# feelerBox1_2.net
KiCad netlist of a schematic drawn in EAGLE
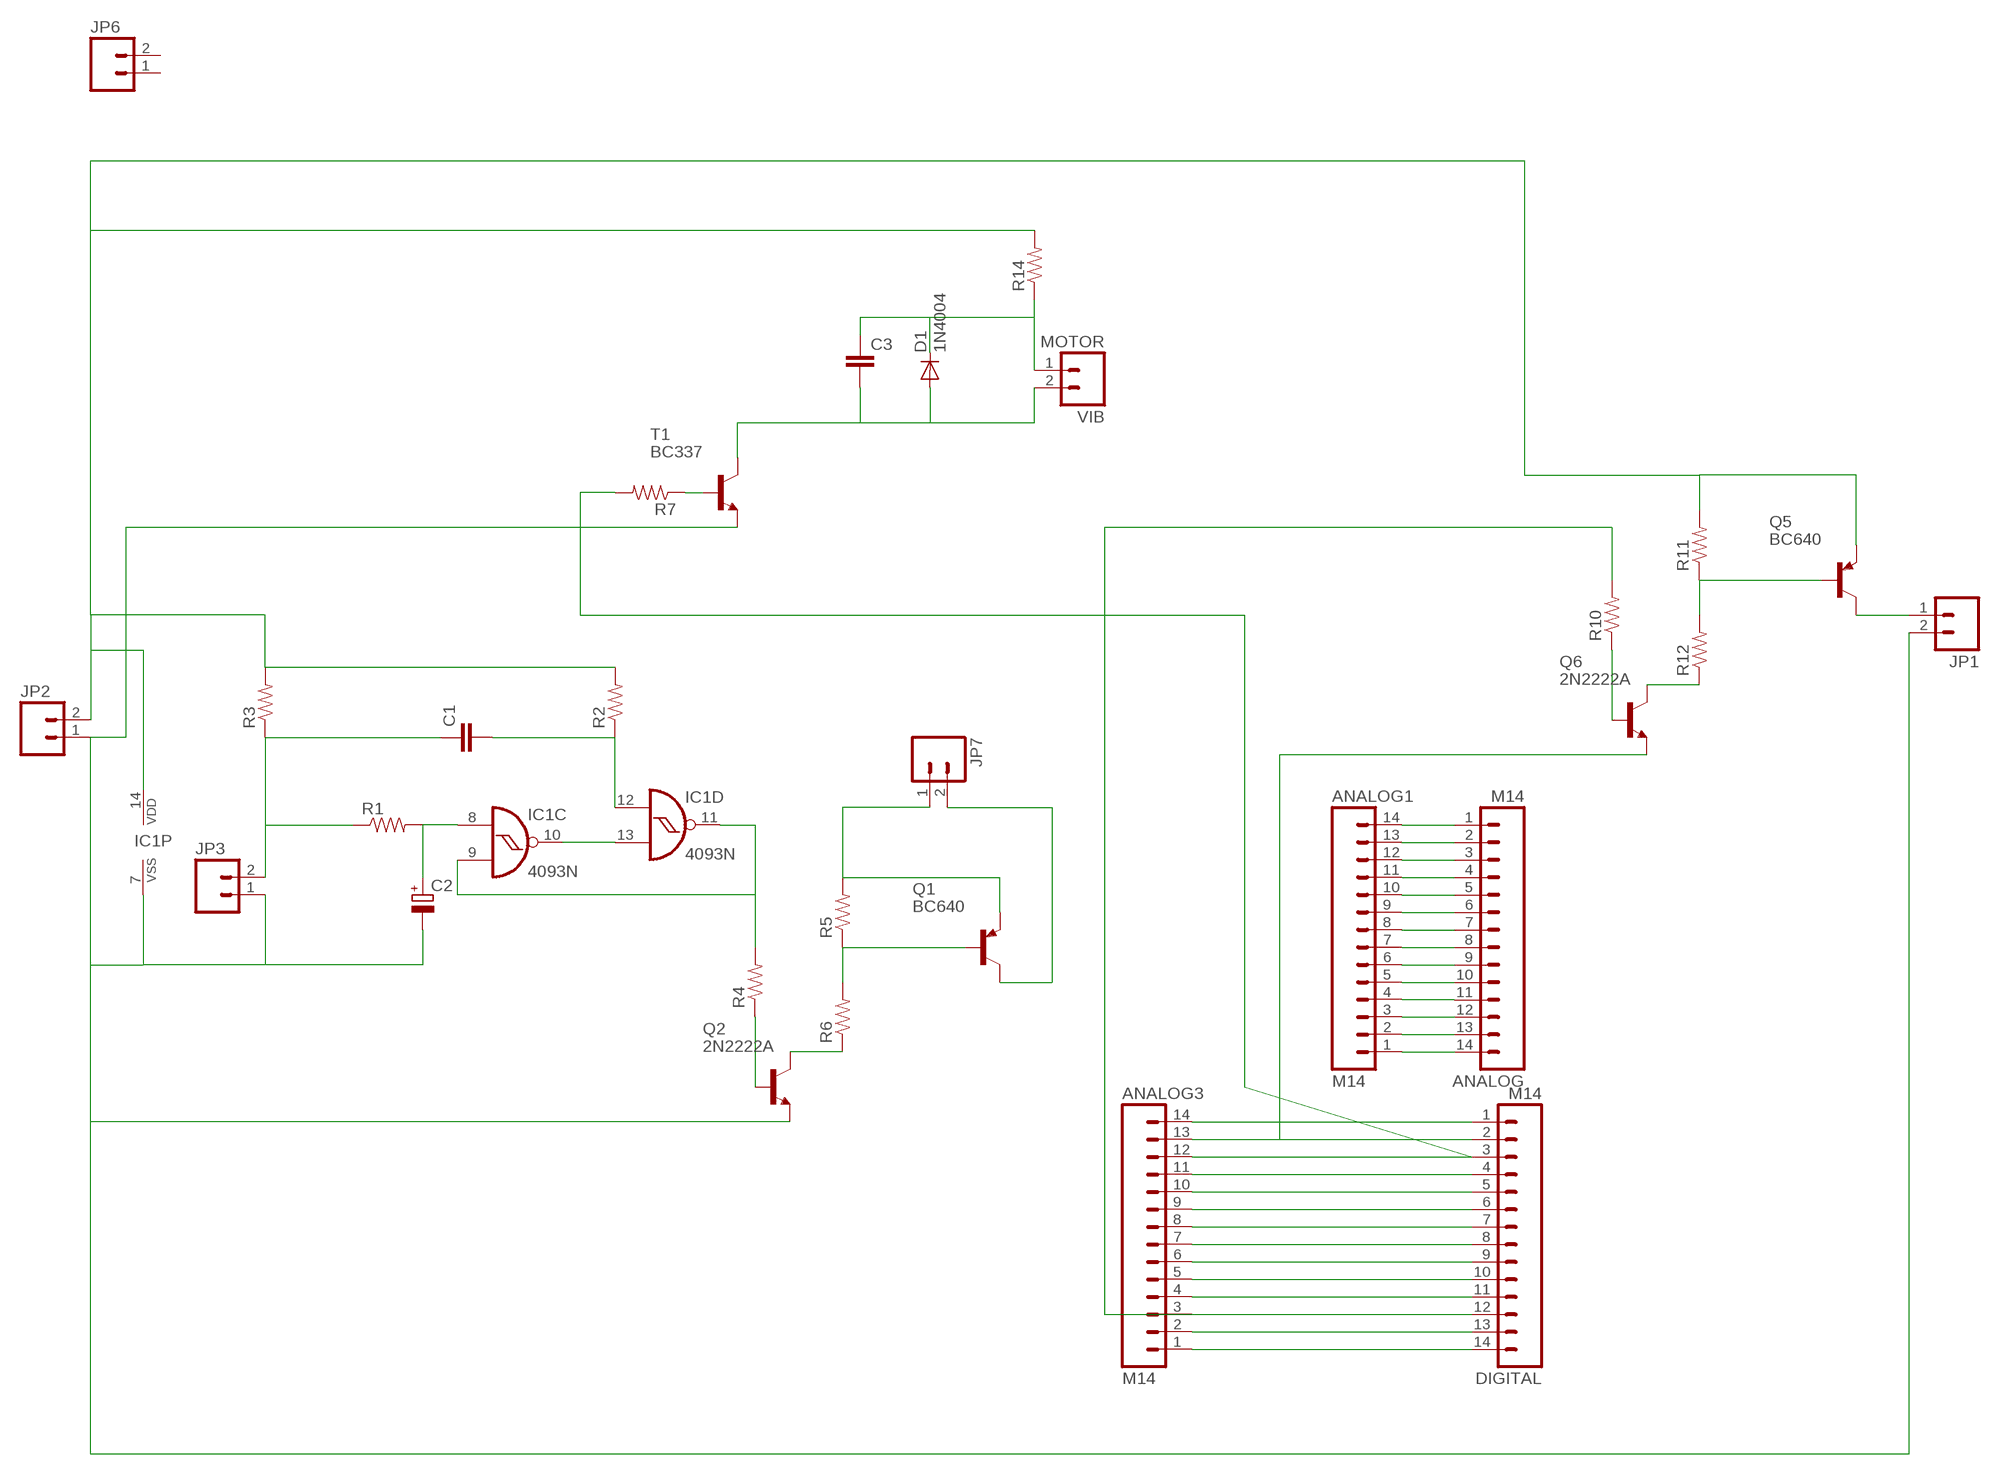
[diagram p0: schematic, sheet 1]

(export (version "E")
  (design (tool "Eeschema 10.0.6"))
  (components
    (comp (ref "ANALOG")
      (value "M14")
      (footprint "eagle-import:1X14")
      (libsource (lib "eagle-import") (part "M14"))
    )
    (comp (ref "ANALOG1")
      (value "M14")
      (footprint "eagle-import:1X14")
      (libsource (lib "eagle-import") (part "M14"))
    )
    (comp (ref "ANALOG3")
      (value "M14")
      (footprint "eagle-import:1X14")
      (libsource (lib "eagle-import") (part "M14"))
    )
    (comp (ref "C1")
      (value "0.1UF-50V-20%(PTH)KIT-EZ")
      (footprint "eagle-import:CAP-PTH-SMALL-KIT")
      (libsource (lib "eagle-import") (part "0.1UF-50V-20%(PTH)KIT-EZ"))
    )
    (comp (ref "C2")
      (value "CPOL-EUE2.5-5")
      (footprint "eagle-import:E2,5-5")
      (libsource (lib "eagle-import") (part "CPOL-EUE2.5-5"))
    )
    (comp (ref "C3")
      (value "CAPKIT")
      (footprint "eagle-import:CAP-PTH-SMALL-KIT")
      (libsource (lib "eagle-import") (part "CAPKIT"))
    )
    (comp (ref "D1")
      (value "1N4004")
      (footprint "eagle-import:DO41-10")
      (libsource (lib "eagle-import") (part "1N4004"))
    )
    (comp (ref "DIGITAL")
      (value "M14")
      (footprint "eagle-import:1X14")
      (libsource (lib "eagle-import") (part "M14"))
    )
    (comp (ref "IC1")
      (value "4093N")
      (footprint "eagle-import:DIL14")
      (libsource (lib "eagle-import") (part "4093N"))
    )
    (comp (ref "JP1")
      (value "M02PTH")
      (footprint "eagle-import:1X02")
      (libsource (lib "eagle-import") (part "M02PTH"))
    )
    (comp (ref "JP2")
      (value "M02PTH")
      (footprint "eagle-import:1X02")
      (libsource (lib "eagle-import") (part "M02PTH"))
    )
    (comp (ref "JP3")
      (value "M02PTH")
      (footprint "eagle-import:1X02")
      (libsource (lib "eagle-import") (part "M02PTH"))
    )
    (comp (ref "JP6")
      (value "M02PTH")
      (footprint "eagle-import:1X02")
      (libsource (lib "eagle-import") (part "M02PTH"))
    )
    (comp (ref "JP7")
      (value "M02PTH")
      (footprint "eagle-import:1X02")
      (libsource (lib "eagle-import") (part "M02PTH"))
    )
    (comp (ref "Q1")
      (value "BC640")
      (footprint "eagle-import:TO92-BCE")
      (libsource (lib "eagle-import") (part "BC640"))
    )
    (comp (ref "Q2")
      (value "2N2222A")
      (footprint "eagle-import:TO18")
      (libsource (lib "eagle-import") (part "2N2222A"))
    )
    (comp (ref "Q5")
      (value "BC640")
      (footprint "eagle-import:TO92-BCE")
      (libsource (lib "eagle-import") (part "BC640"))
    )
    (comp (ref "Q6")
      (value "2N2222A")
      (footprint "eagle-import:TO18")
      (libsource (lib "eagle-import") (part "2N2222A"))
    )
    (comp (ref "R1")
      (value "RESISTORAXIAL-0.3")
      (footprint "eagle-import:AXIAL-0.3")
      (libsource (lib "eagle-import") (part "RESISTORAXIAL-0.3"))
    )
    (comp (ref "R2")
      (value "RESISTORAXIAL-0.3")
      (footprint "eagle-import:AXIAL-0.3")
      (libsource (lib "eagle-import") (part "RESISTORAXIAL-0.3"))
    )
    (comp (ref "R3")
      (value "RESISTORAXIAL-0.3")
      (footprint "eagle-import:AXIAL-0.3")
      (libsource (lib "eagle-import") (part "RESISTORAXIAL-0.3"))
    )
    (comp (ref "R4")
      (value "RESISTORPTH-1/4W-VERT")
      (footprint "eagle-import:AXIAL-0.1")
      (libsource (lib "eagle-import") (part "RESISTORPTH-1/4W-VERT"))
    )
    (comp (ref "R5")
      (value "RESISTORPTH-1/4W-VERT")
      (footprint "eagle-import:AXIAL-0.1")
      (libsource (lib "eagle-import") (part "RESISTORPTH-1/4W-VERT"))
    )
    (comp (ref "R6")
      (value "RESISTORPTH-1/4W-VERT")
      (footprint "eagle-import:AXIAL-0.1")
      (libsource (lib "eagle-import") (part "RESISTORPTH-1/4W-VERT"))
    )
    (comp (ref "R7")
      (value "RESISTORAXIAL-0.3")
      (footprint "eagle-import:AXIAL-0.3")
      (libsource (lib "eagle-import") (part "RESISTORAXIAL-0.3"))
    )
    (comp (ref "R10")
      (value "RESISTORPTH-1/4W-VERT")
      (footprint "eagle-import:AXIAL-0.1")
      (libsource (lib "eagle-import") (part "RESISTORPTH-1/4W-VERT"))
    )
    (comp (ref "R11")
      (value "RESISTORPTH-1/4W-VERT")
      (footprint "eagle-import:AXIAL-0.1")
      (libsource (lib "eagle-import") (part "RESISTORPTH-1/4W-VERT"))
    )
    (comp (ref "R12")
      (value "RESISTORPTH-1/4W-VERT")
      (footprint "eagle-import:AXIAL-0.1")
      (libsource (lib "eagle-import") (part "RESISTORPTH-1/4W-VERT"))
    )
    (comp (ref "R14")
      (value "RESISTORPTH-1/4W-VERT")
      (footprint "eagle-import:AXIAL-0.1")
      (libsource (lib "eagle-import") (part "RESISTORPTH-1/4W-VERT"))
    )
    (comp (ref "T1")
      (value "BC337")
      (footprint "eagle-import:TO92")
      (libsource (lib "eagle-import") (part "BC337"))
    )
    (comp (ref "VIB")
      (value "MOTOR")
      (footprint "eagle-import:1X02")
      (libsource (lib "eagle-import") (part "M02PTH"))
    )
  )
  (nets
    (net (code "1") (name "Net-(ANALOG-Pad1)") (class "Default")
      (node (ref "ANALOG") (pin "1") (pinfunction "1_1") (pintype "passive"))
      (node (ref "ANALOG1") (pin "14") (pinfunction "14_14") (pintype "passive"))
    )
    (net (code "2") (name "Net-(ANALOG-Pad2)") (class "Default")
      (node (ref "ANALOG") (pin "2") (pinfunction "2_2") (pintype "passive"))
      (node (ref "ANALOG1") (pin "13") (pinfunction "13_13") (pintype "passive"))
    )
    (net (code "3") (name "Net-(ANALOG-Pad3)") (class "Default")
      (node (ref "ANALOG") (pin "3") (pinfunction "3_3") (pintype "passive"))
      (node (ref "ANALOG1") (pin "12") (pinfunction "12_12") (pintype "passive"))
    )
    (net (code "4") (name "Net-(ANALOG-Pad4)") (class "Default")
      (node (ref "ANALOG") (pin "4") (pinfunction "4_4") (pintype "passive"))
      (node (ref "ANALOG1") (pin "11") (pinfunction "11_11") (pintype "passive"))
    )
    (net (code "5") (name "Net-(ANALOG-Pad5)") (class "Default")
      (node (ref "ANALOG") (pin "5") (pinfunction "5_5") (pintype "passive"))
      (node (ref "ANALOG1") (pin "10") (pinfunction "10_10") (pintype "passive"))
    )
    (net (code "6") (name "Net-(ANALOG-Pad6)") (class "Default")
      (node (ref "ANALOG") (pin "6") (pinfunction "6_6") (pintype "passive"))
      (node (ref "ANALOG1") (pin "9") (pinfunction "9_9") (pintype "passive"))
    )
    (net (code "7") (name "Net-(ANALOG-Pad7)") (class "Default")
      (node (ref "ANALOG") (pin "7") (pinfunction "7_7") (pintype "passive"))
      (node (ref "ANALOG1") (pin "8") (pinfunction "8_8") (pintype "passive"))
    )
    (net (code "8") (name "Net-(ANALOG-Pad8)") (class "Default")
      (node (ref "ANALOG") (pin "8") (pinfunction "8_8") (pintype "passive"))
      (node (ref "ANALOG1") (pin "7") (pinfunction "7_7") (pintype "passive"))
    )
    (net (code "9") (name "Net-(ANALOG-Pad9)") (class "Default")
      (node (ref "ANALOG") (pin "9") (pinfunction "9_9") (pintype "passive"))
      (node (ref "ANALOG1") (pin "6") (pinfunction "6_6") (pintype "passive"))
    )
    (net (code "10") (name "Net-(ANALOG-Pad10)") (class "Default")
      (node (ref "ANALOG") (pin "10") (pinfunction "10_10") (pintype "passive"))
      (node (ref "ANALOG1") (pin "5") (pinfunction "5_5") (pintype "passive"))
    )
    (net (code "11") (name "Net-(ANALOG-Pad11)") (class "Default")
      (node (ref "ANALOG") (pin "11") (pinfunction "11_11") (pintype "passive"))
      (node (ref "ANALOG1") (pin "4") (pinfunction "4_4") (pintype "passive"))
    )
    (net (code "12") (name "Net-(ANALOG-Pad12)") (class "Default")
      (node (ref "ANALOG") (pin "12") (pinfunction "12_12") (pintype "passive"))
      (node (ref "ANALOG1") (pin "3") (pinfunction "3_3") (pintype "passive"))
    )
    (net (code "13") (name "Net-(ANALOG-Pad13)") (class "Default")
      (node (ref "ANALOG") (pin "13") (pinfunction "13_13") (pintype "passive"))
      (node (ref "ANALOG1") (pin "2") (pinfunction "2_2") (pintype "passive"))
    )
    (net (code "14") (name "Net-(ANALOG-Pad14)") (class "Default")
      (node (ref "ANALOG") (pin "14") (pinfunction "14_14") (pintype "passive"))
      (node (ref "ANALOG1") (pin "1") (pinfunction "1_1") (pintype "passive"))
    )
    (net (code "15") (name "Net-(ANALOG3-Pad1)") (class "Default")
      (node (ref "ANALOG3") (pin "1") (pinfunction "1_1") (pintype "passive"))
      (node (ref "DIGITAL") (pin "14") (pinfunction "14_14") (pintype "passive"))
    )
    (net (code "16") (name "Net-(ANALOG3-Pad2)") (class "Default")
      (node (ref "ANALOG3") (pin "2") (pinfunction "2_2") (pintype "passive"))
      (node (ref "DIGITAL") (pin "13") (pinfunction "13_13") (pintype "passive"))
    )
    (net (code "17") (name "Net-(ANALOG3-Pad4)") (class "Default")
      (node (ref "ANALOG3") (pin "4") (pinfunction "4_4") (pintype "passive"))
      (node (ref "DIGITAL") (pin "11") (pinfunction "11_11") (pintype "passive"))
    )
    (net (code "18") (name "Net-(ANALOG3-Pad5)") (class "Default")
      (node (ref "ANALOG3") (pin "5") (pinfunction "5_5") (pintype "passive"))
      (node (ref "DIGITAL") (pin "10") (pinfunction "10_10") (pintype "passive"))
    )
    (net (code "19") (name "Net-(ANALOG3-Pad6)") (class "Default")
      (node (ref "ANALOG3") (pin "6") (pinfunction "6_6") (pintype "passive"))
      (node (ref "DIGITAL") (pin "9") (pinfunction "9_9") (pintype "passive"))
    )
    (net (code "20") (name "Net-(ANALOG3-Pad7)") (class "Default")
      (node (ref "ANALOG3") (pin "7") (pinfunction "7_7") (pintype "passive"))
      (node (ref "DIGITAL") (pin "8") (pinfunction "8_8") (pintype "passive"))
    )
    (net (code "21") (name "Net-(ANALOG3-Pad8)") (class "Default")
      (node (ref "ANALOG3") (pin "8") (pinfunction "8_8") (pintype "passive"))
      (node (ref "DIGITAL") (pin "7") (pinfunction "7_7") (pintype "passive"))
    )
    (net (code "22") (name "Net-(ANALOG3-Pad9)") (class "Default")
      (node (ref "ANALOG3") (pin "9") (pinfunction "9_9") (pintype "passive"))
      (node (ref "DIGITAL") (pin "6") (pinfunction "6_6") (pintype "passive"))
    )
    (net (code "23") (name "Net-(ANALOG3-Pad10)") (class "Default")
      (node (ref "ANALOG3") (pin "10") (pinfunction "10_10") (pintype "passive"))
      (node (ref "DIGITAL") (pin "5") (pinfunction "5_5") (pintype "passive"))
    )
    (net (code "24") (name "Net-(ANALOG3-Pad11)") (class "Default")
      (node (ref "ANALOG3") (pin "11") (pinfunction "11_11") (pintype "passive"))
      (node (ref "DIGITAL") (pin "4") (pinfunction "4_4") (pintype "passive"))
    )
    (net (code "25") (name "Net-(ANALOG3-Pad14)") (class "Default")
      (node (ref "ANALOG3") (pin "14") (pinfunction "14_14") (pintype "passive"))
      (node (ref "DIGITAL") (pin "1") (pinfunction "1_1") (pintype "passive"))
    )
    (net (code "26") (name "Net-(IC1C-I0)") (class "Default")
      (node (ref "C2") (pin "+") (pinfunction "+_+") (pintype "passive"))
      (node (ref "IC1") (pin "8") (pinfunction "I0_8") (pintype "input"))
      (node (ref "R1") (pin "P$2") (pinfunction "2_P$2") (pintype "passive"))
    )
    (net (code "27") (name "Net-(IC1C-I1)") (class "Default")
      (node (ref "IC1") (pin "11") (pinfunction "O_11") (pintype "output"))
      (node (ref "IC1") (pin "9") (pinfunction "I1_9") (pintype "input"))
      (node (ref "R4") (pin "P$2") (pinfunction "2_P$2") (pintype "passive"))
    )
    (net (code "28") (name "Net-(IC1C-O)") (class "Default")
      (node (ref "IC1") (pin "10") (pinfunction "O_10") (pintype "output"))
      (node (ref "IC1") (pin "13") (pinfunction "I1_13") (pintype "input"))
    )
    (net (code "29") (name "Net-(IC1D-I0)") (class "Default")
      (node (ref "C1") (pin "2") (pinfunction "2_2") (pintype "passive"))
      (node (ref "IC1") (pin "12") (pinfunction "I0_12") (pintype "input"))
      (node (ref "R2") (pin "P$1") (pinfunction "1_P$1") (pintype "passive"))
    )
    (net (code "30") (name "Net-(IC1E-VDD)") (class "Default")
      (node (ref "IC1") (pin "14") (pinfunction "VDD_14") (pintype "power_in"))
      (node (ref "JP2") (pin "2") (pinfunction "2_2") (pintype "passive"))
      (node (ref "Q5") (pin "E") (pinfunction "E_E") (pintype "passive"))
      (node (ref "R11") (pin "P$2") (pinfunction "2_P$2") (pintype "passive"))
      (node (ref "R14") (pin "P$2") (pinfunction "2_P$2") (pintype "passive"))
      (node (ref "R2") (pin "P$2") (pinfunction "2_P$2") (pintype "passive"))
      (node (ref "R3") (pin "P$2") (pinfunction "2_P$2") (pintype "passive"))
    )
    (net (code "31") (name "Net-(IC1E-VSS)") (class "Default")
      (node (ref "C2") (pin "-") (pinfunction "-_-") (pintype "passive"))
      (node (ref "IC1") (pin "7") (pinfunction "VSS_7") (pintype "power_in"))
      (node (ref "JP1") (pin "2") (pinfunction "2_2") (pintype "passive"))
      (node (ref "JP2") (pin "1") (pinfunction "1_1") (pintype "passive"))
      (node (ref "JP3") (pin "1") (pinfunction "1_1") (pintype "passive"))
      (node (ref "Q2") (pin "1") (pinfunction "E_1") (pintype "passive"))
      (node (ref "T1") (pin "1") (pinfunction "E_1") (pintype "passive"))
    )
    (net (code "32") (name "Net-(JP1-Pad1)") (class "Default")
      (node (ref "JP1") (pin "1") (pinfunction "1_1") (pintype "passive"))
      (node (ref "Q5") (pin "C") (pinfunction "C_C") (pintype "passive"))
    )
    (net (code "33") (name "Net-(JP7-Pad2)") (class "Default")
      (node (ref "JP7") (pin "2") (pinfunction "2_2") (pintype "passive"))
      (node (ref "Q1") (pin "C") (pinfunction "C_C") (pintype "passive"))
    )
    (net (code "34") (name "Net-(Q2-B)") (class "Default")
      (node (ref "Q2") (pin "2") (pinfunction "B_2") (pintype "passive"))
      (node (ref "R4") (pin "P$1") (pinfunction "1_P$1") (pintype "passive"))
    )
    (net (code "35") (name "Net-(Q2-C)") (class "Default")
      (node (ref "Q2") (pin "3") (pinfunction "C_3") (pintype "passive"))
      (node (ref "R6") (pin "P$1") (pinfunction "1_P$1") (pintype "passive"))
    )
    (net (code "36") (name "Net-(Q6-B)") (class "Default")
      (node (ref "Q6") (pin "2") (pinfunction "B_2") (pintype "passive"))
      (node (ref "R10") (pin "P$1") (pinfunction "1_P$1") (pintype "passive"))
    )
    (net (code "37") (name "Net-(Q6-C)") (class "Default")
      (node (ref "Q6") (pin "3") (pinfunction "C_3") (pintype "passive"))
      (node (ref "R12") (pin "P$1") (pinfunction "1_P$1") (pintype "passive"))
    )
    (net (code "38") (name "Net-(Q6-E)") (class "Default")
      (node (ref "ANALOG3") (pin "13") (pinfunction "13_13") (pintype "passive"))
      (node (ref "DIGITAL") (pin "2") (pinfunction "2_2") (pintype "passive"))
      (node (ref "Q6") (pin "1") (pinfunction "E_1") (pintype "passive"))
    )
    (net (code "39") (name "Net-(R1-1)") (class "Default")
      (node (ref "C1") (pin "1") (pinfunction "1_1") (pintype "passive"))
      (node (ref "JP3") (pin "2") (pinfunction "2_2") (pintype "passive"))
      (node (ref "R1") (pin "P$1") (pinfunction "1_P$1") (pintype "passive"))
      (node (ref "R3") (pin "P$1") (pinfunction "1_P$1") (pintype "passive"))
    )
    (net (code "40") (name "Net-(R5-1)") (class "Default")
      (node (ref "Q1") (pin "B") (pinfunction "B_B") (pintype "passive"))
      (node (ref "R5") (pin "P$1") (pinfunction "1_P$1") (pintype "passive"))
      (node (ref "R6") (pin "P$2") (pinfunction "2_P$2") (pintype "passive"))
    )
    (net (code "41") (name "Net-(R5-2)") (class "Default")
      (node (ref "JP7") (pin "1") (pinfunction "1_1") (pintype "passive"))
      (node (ref "Q1") (pin "E") (pinfunction "E_E") (pintype "passive"))
      (node (ref "R5") (pin "P$2") (pinfunction "2_P$2") (pintype "passive"))
    )
    (net (code "42") (name "Net-(R7-1)") (class "Default")
      (node (ref "R7") (pin "P$1") (pinfunction "1_P$1") (pintype "passive"))
      (node (ref "T1") (pin "2") (pinfunction "B_2") (pintype "passive"))
    )
    (net (code "43") (name "Net-(R7-2)") (class "Default")
      (node (ref "ANALOG3") (pin "12") (pinfunction "12_12") (pintype "passive"))
      (node (ref "DIGITAL") (pin "3") (pinfunction "3_3") (pintype "passive"))
      (node (ref "R7") (pin "P$2") (pinfunction "2_P$2") (pintype "passive"))
    )
    (net (code "44") (name "Net-(R10-2)") (class "Default")
      (node (ref "ANALOG3") (pin "3") (pinfunction "3_3") (pintype "passive"))
      (node (ref "DIGITAL") (pin "12") (pinfunction "12_12") (pintype "passive"))
      (node (ref "R10") (pin "P$2") (pinfunction "2_P$2") (pintype "passive"))
    )
    (net (code "45") (name "Net-(R11-1)") (class "Default")
      (node (ref "Q5") (pin "B") (pinfunction "B_B") (pintype "passive"))
      (node (ref "R11") (pin "P$1") (pinfunction "1_P$1") (pintype "passive"))
      (node (ref "R12") (pin "P$2") (pinfunction "2_P$2") (pintype "passive"))
    )
    (net (code "46") (name "Net-(R14-1)") (class "Default")
      (node (ref "C3") (pin "1") (pinfunction "1_1") (pintype "passive"))
      (node (ref "D1") (pin "C") (pinfunction "C_C") (pintype "passive"))
      (node (ref "R14") (pin "P$1") (pinfunction "1_P$1") (pintype "passive"))
      (node (ref "VIB") (pin "1") (pinfunction "1_1") (pintype "passive"))
    )
    (net (code "47") (name "Net-(T1-C)") (class "Default")
      (node (ref "C3") (pin "2") (pinfunction "2_2") (pintype "passive"))
      (node (ref "D1") (pin "A") (pinfunction "A_A") (pintype "passive"))
      (node (ref "T1") (pin "3") (pinfunction "C_3") (pintype "passive"))
      (node (ref "VIB") (pin "2") (pinfunction "2_2") (pintype "passive"))
    )
    (net (code "48") (name "unconnected-(JP6-Pad1)") (class "Default")
      (node (ref "JP6") (pin "1") (pinfunction "1_1") (pintype "passive"))
    )
    (net (code "49") (name "unconnected-(JP6-Pad2)") (class "Default")
      (node (ref "JP6") (pin "2") (pinfunction "2_2") (pintype "passive"))
    )
  )
)
